# Power_Supply.net
KiCad netlist of a schematic drawn in Altium Designer
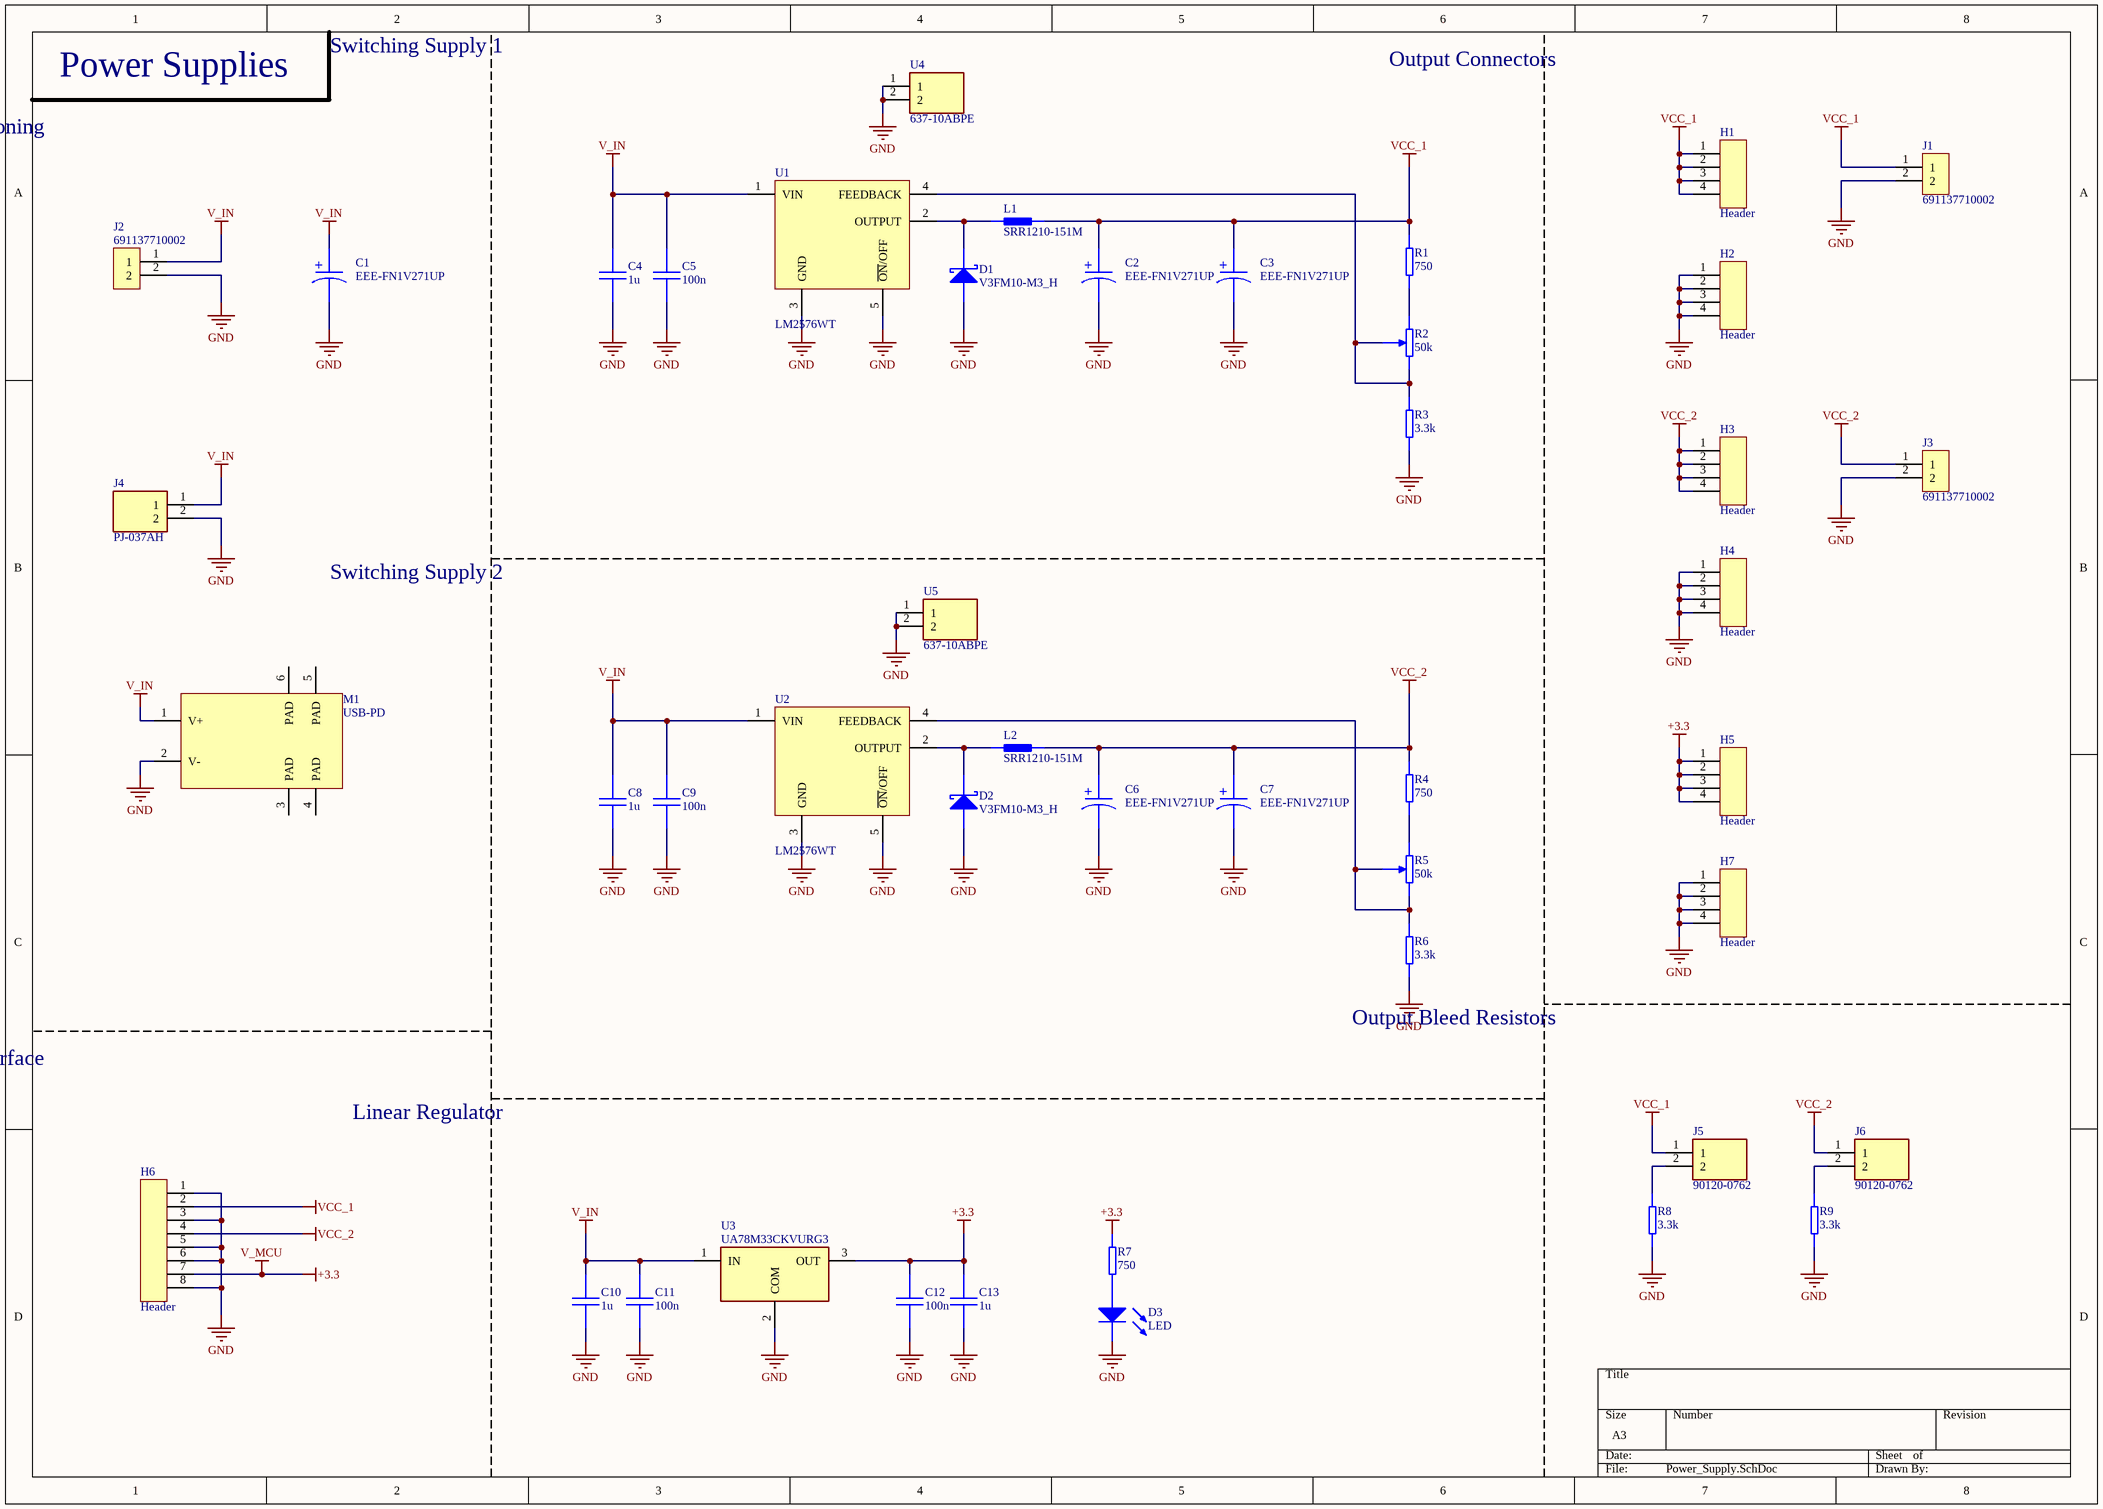
[diagram p0: Power_Supply.SchDoc]

(export (version "E")
  (design (tool "Eeschema 10.0.6"))
  (components
    (comp (ref "C1")
      (value "EEE-FN1V271UP")
      (footprint "EEHZT1E331UP")
      (description "Capacitor Polarised")
      (fields (field (name "MOUSER PART NUMBER") "667-EEE-FN1V271UP"))
      (libsource (lib "TD") (part "EEE-FN1V271UP"))
    )
    (comp (ref "C2")
      (value "EEE-FN1V271UP")
      (footprint "EEHZT1E331UP")
      (description "Capacitor Polarised")
      (fields (field (name "MOUSER PART NUMBER") "667-EEE-FN1V271UP"))
      (libsource (lib "TD") (part "EEE-FN1V271UP"))
    )
    (comp (ref "C3")
      (value "EEE-FN1V271UP")
      (footprint "EEHZT1E331UP")
      (description "Capacitor Polarised")
      (fields (field (name "MOUSER PART NUMBER") "667-EEE-FN1V271UP"))
      (libsource (lib "TD") (part "EEE-FN1V271UP"))
    )
    (comp (ref "C4")
      (value "1u")
      (footprint "CAP0805")
      (description "Non Polarized Capacitor")
      (libsource (lib "TD") (part "Capacitor - Non Polarized"))
    )
    (comp (ref "C5")
      (value "100n")
      (footprint "CAP0805")
      (description "Non Polarized Capacitor")
      (libsource (lib "TD") (part "Capacitor - Non Polarized"))
    )
    (comp (ref "C6")
      (value "EEE-FN1V271UP")
      (footprint "EEHZT1E331UP")
      (description "Capacitor Polarised")
      (fields (field (name "MOUSER PART NUMBER") "667-EEE-FN1V271UP"))
      (libsource (lib "TD") (part "EEE-FN1V271UP"))
    )
    (comp (ref "C7")
      (value "EEE-FN1V271UP")
      (footprint "EEHZT1E331UP")
      (description "Capacitor Polarised")
      (fields (field (name "MOUSER PART NUMBER") "667-EEE-FN1V271UP"))
      (libsource (lib "TD") (part "EEE-FN1V271UP"))
    )
    (comp (ref "C8")
      (value "1u")
      (footprint "CAP0805")
      (description "Non Polarized Capacitor")
      (libsource (lib "TD") (part "Capacitor - Non Polarized"))
    )
    (comp (ref "C9")
      (value "100n")
      (footprint "CAP0805")
      (description "Non Polarized Capacitor")
      (libsource (lib "TD") (part "Capacitor - Non Polarized"))
    )
    (comp (ref "C10")
      (value "1u")
      (footprint "CAP0805")
      (description "Non Polarized Capacitor")
      (libsource (lib "TD") (part "Capacitor - Non Polarized"))
    )
    (comp (ref "C11")
      (value "100n")
      (footprint "CAP0805")
      (description "Non Polarized Capacitor")
      (libsource (lib "TD") (part "Capacitor - Non Polarized"))
    )
    (comp (ref "C12")
      (value "100n")
      (footprint "CAP0805")
      (description "Non Polarized Capacitor")
      (libsource (lib "TD") (part "Capacitor - Non Polarized"))
    )
    (comp (ref "C13")
      (value "1u")
      (footprint "CAP0805")
      (description "Non Polarized Capacitor")
      (libsource (lib "TD") (part "Capacitor - Non Polarized"))
    )
    (comp (ref "D1")
      (value "V3FM10-M3_H")
      (footprint "DO-219AB")
      (description "Schottky Diode")
      (fields
        (field (name "MANUFACTURER_PART_NUMBER") "V3FM10-M3/H")
        (field (name "MOUSER PART NUMBER") "78-V3FM10-M3/H")
      )
      (libsource (lib "TD") (part "V3FM10-M3_H"))
    )
    (comp (ref "D2")
      (value "V3FM10-M3_H")
      (footprint "DO-219AB")
      (description "Schottky Diode")
      (fields
        (field (name "MANUFACTURER_PART_NUMBER") "V3FM10-M3/H")
        (field (name "MOUSER PART NUMBER") "78-V3FM10-M3/H")
      )
      (libsource (lib "TD") (part "V3FM10-M3_H"))
    )
    (comp (ref "D3")
      (value "LED")
      (footprint "LEDM2012X80N")
      (description "General Purpose LED")
      (libsource (lib "TD") (part "LED"))
    )
    (comp (ref "H1")
      (value "Header")
      (footprint "Header_1X4")
      (description "4-Pin Header")
      (libsource (lib "TD") (part "4-Pin Header"))
    )
    (comp (ref "H2")
      (value "Header")
      (footprint "Header_1X4")
      (description "4-Pin Header")
      (libsource (lib "TD") (part "4-Pin Header"))
    )
    (comp (ref "H3")
      (value "Header")
      (footprint "Header_1X4")
      (description "4-Pin Header")
      (libsource (lib "TD") (part "4-Pin Header"))
    )
    (comp (ref "H4")
      (value "Header")
      (footprint "Header_1X4")
      (description "4-Pin Header")
      (libsource (lib "TD") (part "4-Pin Header"))
    )
    (comp (ref "H5")
      (value "Header")
      (footprint "Header_1X4")
      (description "4-Pin Header")
      (libsource (lib "TD") (part "4-Pin Header"))
    )
    (comp (ref "H6")
      (value "Header")
      (footprint "Header_1X8")
      (description "8-Pin Header")
      (libsource (lib "TD") (part "8-Pin Header"))
    )
    (comp (ref "H7")
      (value "Header")
      (footprint "Header_1X4")
      (description "4-Pin Header")
      (libsource (lib "TD") (part "4-Pin Header"))
    )
    (comp (ref "J1")
      (value "691137710002")
      (footprint "SHDR2W70P0X500_1X2_1000X750X1160P")
      (description "Connector")
      (fields (field (name "MOUSER PART NUMBER") "710-691137710002"))
      (libsource (lib "") (part "691137710002_1"))
    )
    (comp (ref "J2")
      (value "691137710002")
      (footprint "SHDR2W70P0X500_1X2_1000X750X1160P")
      (description "Connector")
      (fields (field (name "MOUSER PART NUMBER") "710-691137710002"))
      (libsource (lib "TD") (part "691137710002"))
    )
    (comp (ref "J3")
      (value "691137710002")
      (footprint "SHDR2W70P0X500_1X2_1000X750X1160P")
      (description "Connector")
      (fields (field (name "MOUSER PART NUMBER") "710-691137710002"))
      (libsource (lib "") (part "691137710002_1"))
    )
    (comp (ref "J4")
      (value "PJ-037AH")
      (footprint "PJ037AH")
      (description "Connector")
      (fields (field (name "MOUSER PART NUMBER") "490-PJ-037AH"))
      (libsource (lib "TD") (part "PJ-037AH"))
    )
    (comp (ref "J5")
      (value "90120-0762")
      (footprint "HDRV2W35P0X254_1X2_508X249X560P")
      (description "Connector")
      (fields (field (name "MOUSER PART NUMBER") "538-90120-0762"))
      (libsource (lib "SamacSys") (part "90120-0762"))
    )
    (comp (ref "J6")
      (value "90120-0762")
      (footprint "HDRV2W35P0X254_1X2_508X249X560P")
      (description "Connector")
      (fields (field (name "MOUSER PART NUMBER") "538-90120-0762"))
      (libsource (lib "SamacSys") (part "90120-0762"))
    )
    (comp (ref "L1")
      (value "SRR1210-151M")
      (footprint "INDPM120120X1000N-D")
      (description "Inductor")
      (fields (field (name "MOUSER PART NUMBER") "652-SRR1210-151M"))
      (libsource (lib "TD") (part "SRR1210-151M"))
    )
    (comp (ref "L2")
      (value "SRR1210-151M")
      (footprint "INDPM120120X1000N-D")
      (description "Inductor")
      (fields (field (name "MOUSER PART NUMBER") "652-SRR1210-151M"))
      (libsource (lib "TD") (part "SRR1210-151M"))
    )
    (comp (ref "M1")
      (value "USB-PD")
      (footprint "USB_C-PD")
      (libsource (lib "IEEE_Workshop_SCH") (part "USB-PD"))
    )
    (comp (ref "R1")
      (value "750")
      (footprint "RESC0805")
      (description "Resistor")
      (libsource (lib "TD") (part "Resistor"))
    )
    (comp (ref "R2")
      (value "50k")
      (footprint "3339P1103LF")
      (description "Potentionmeter")
      (libsource (lib "TD") (part "Potentiometer"))
    )
    (comp (ref "R3")
      (value "3.3k")
      (footprint "RESC0805")
      (description "Resistor")
      (libsource (lib "TD") (part "Resistor"))
    )
    (comp (ref "R4")
      (value "750")
      (footprint "RESC0805")
      (description "Resistor")
      (libsource (lib "TD") (part "Resistor"))
    )
    (comp (ref "R5")
      (value "50k")
      (footprint "3339P1103LF")
      (description "Potentionmeter")
      (libsource (lib "TD") (part "Potentiometer"))
    )
    (comp (ref "R6")
      (value "3.3k")
      (footprint "RESC0805")
      (description "Resistor")
      (libsource (lib "TD") (part "Resistor"))
    )
    (comp (ref "R7")
      (value "750")
      (footprint "RESC0805")
      (description "Resistor")
      (libsource (lib "TD") (part "Resistor"))
    )
    (comp (ref "R8")
      (value "3.3k")
      (footprint "RESC0805")
      (description "Resistor")
      (libsource (lib "TD") (part "Resistor"))
    )
    (comp (ref "R9")
      (value "3.3k")
      (footprint "RESC0805")
      (description "Resistor")
      (libsource (lib "TD") (part "Resistor"))
    )
    (comp (ref "U1")
      (value "LM2576WT")
      (footprint "TO-220-5")
      (description "Integrated Circuit")
      (fields
        (field (name "MANUFACTURER_PART_NUMBER") "LM2576WU-TR")
        (field (name "MOUSER PART NUMBER") "998-LM2576WT")
      )
      (libsource (lib "IEEE_Workshop_Schematic_Symbols") (part "LM2576WT"))
    )
    (comp (ref "U2")
      (value "LM2576WT")
      (footprint "TO-220-5")
      (description "Integrated Circuit")
      (fields
        (field (name "MANUFACTURER_PART_NUMBER") "LM2576WU-TR")
        (field (name "MOUSER PART NUMBER") "998-LM2576WT")
      )
      (libsource (lib "IEEE_Workshop_Schematic_Symbols") (part "LM2576WT"))
    )
    (comp (ref "U3")
      (value "UA78M33CKVURG3")
      (footprint "TO-252-3")
      (description "Linear Voltage Regulator")
      (fields (field (name "MOUSER PART NUMBER") "595-UA78M33CKVURG3"))
      (libsource (lib "TD") (part "UA78M33CKVURG3"))
    )
    (comp (ref "U4")
      (value "637-10ABPE")
      (footprint "63710ABPE")
      (description "Undefined or Miscellaneous")
      (fields (field (name "MOUSER PART NUMBER") "567-637-10ABPE"))
      (libsource (lib "*") (part "637-10ABPE"))
    )
    (comp (ref "U5")
      (value "637-10ABPE")
      (footprint "63710ABPE")
      (description "Undefined or Miscellaneous")
      (fields (field (name "MOUSER PART NUMBER") "567-637-10ABPE"))
      (libsource (lib "*") (part "637-10ABPE"))
    )
  )
  (nets
    (net (code "1") (name "+3.3") (class "Default")
      (node (ref "C12") (pin "1") (pintype "passive"))
      (node (ref "C13") (pin "1") (pintype "passive"))
      (node (ref "H5") (pin "1") (pintype "passive"))
      (node (ref "H5") (pin "2") (pintype "passive"))
      (node (ref "H5") (pin "3") (pintype "passive"))
      (node (ref "H5") (pin "4") (pintype "passive"))
      (node (ref "H6") (pin "7") (pintype "passive"))
      (node (ref "R7") (pin "1") (pintype "passive"))
      (node (ref "U3") (pin "3") (pinfunction "OUT_3") (pintype "passive"))
    )
    (net (code "2") (name "GND") (class "Default")
      (node (ref "C1") (pin "2") (pintype "passive"))
      (node (ref "C10") (pin "2") (pintype "passive"))
      (node (ref "C11") (pin "2") (pintype "passive"))
      (node (ref "C12") (pin "2") (pintype "passive"))
      (node (ref "C13") (pin "2") (pintype "passive"))
      (node (ref "C2") (pin "2") (pintype "passive"))
      (node (ref "C3") (pin "2") (pintype "passive"))
      (node (ref "C4") (pin "2") (pintype "passive"))
      (node (ref "C5") (pin "2") (pintype "passive"))
      (node (ref "C6") (pin "2") (pintype "passive"))
      (node (ref "C7") (pin "2") (pintype "passive"))
      (node (ref "C8") (pin "2") (pintype "passive"))
      (node (ref "C9") (pin "2") (pintype "passive"))
      (node (ref "D1") (pin "2") (pinfunction "A_2") (pintype "passive"))
      (node (ref "D2") (pin "2") (pinfunction "A_2") (pintype "passive"))
      (node (ref "D3") (pin "1") (pinfunction "K_1") (pintype "passive"))
      (node (ref "H2") (pin "1") (pintype "passive"))
      (node (ref "H2") (pin "2") (pintype "passive"))
      (node (ref "H2") (pin "3") (pintype "passive"))
      (node (ref "H2") (pin "4") (pintype "passive"))
      (node (ref "H4") (pin "1") (pintype "passive"))
      (node (ref "H4") (pin "2") (pintype "passive"))
      (node (ref "H4") (pin "3") (pintype "passive"))
      (node (ref "H4") (pin "4") (pintype "passive"))
      (node (ref "H6") (pin "1") (pintype "passive"))
      (node (ref "H6") (pin "3") (pintype "passive"))
      (node (ref "H6") (pin "5") (pintype "passive"))
      (node (ref "H6") (pin "6") (pintype "passive"))
      (node (ref "H6") (pin "8") (pintype "passive"))
      (node (ref "H7") (pin "1") (pintype "passive"))
      (node (ref "H7") (pin "2") (pintype "passive"))
      (node (ref "H7") (pin "3") (pintype "passive"))
      (node (ref "H7") (pin "4") (pintype "passive"))
      (node (ref "J1") (pin "2") (pinfunction "2_2") (pintype "passive"))
      (node (ref "J2") (pin "2") (pinfunction "2_2") (pintype "passive"))
      (node (ref "J3") (pin "2") (pinfunction "2_2") (pintype "passive"))
      (node (ref "J4") (pin "2") (pinfunction "2_2") (pintype "passive"))
      (node (ref "M1") (pin "2") (pinfunction "V-_2") (pintype "passive"))
      (node (ref "R3") (pin "2") (pintype "passive"))
      (node (ref "R6") (pin "2") (pintype "passive"))
      (node (ref "R8") (pin "2") (pintype "passive"))
      (node (ref "R9") (pin "2") (pintype "passive"))
      (node (ref "U1") (pin "3") (pinfunction "GND_3") (pintype "passive"))
      (node (ref "U1") (pin "5") (pinfunction "~{ON}/OFF_5") (pintype "passive"))
      (node (ref "U2") (pin "3") (pinfunction "GND_3") (pintype "passive"))
      (node (ref "U2") (pin "5") (pinfunction "~{ON}/OFF_5") (pintype "passive"))
      (node (ref "U3") (pin "2") (pinfunction "COM_2") (pintype "passive"))
      (node (ref "U4") (pin "1") (pinfunction "1_1") (pintype "passive"))
      (node (ref "U4") (pin "2") (pinfunction "2_2") (pintype "passive"))
      (node (ref "U5") (pin "1") (pinfunction "1_1") (pintype "passive"))
      (node (ref "U5") (pin "2") (pinfunction "2_2") (pintype "passive"))
    )
    (net (code "3") (name "Net-(D1-K)") (class "Default")
      (node (ref "D1") (pin "1") (pinfunction "K_1") (pintype "passive"))
      (node (ref "L1") (pin "1") (pintype "passive"))
      (node (ref "U1") (pin "2") (pinfunction "OUTPUT_2") (pintype "passive"))
    )
    (net (code "4") (name "Net-(D2-K)") (class "Default")
      (node (ref "D2") (pin "1") (pinfunction "K_1") (pintype "passive"))
      (node (ref "L2") (pin "1") (pintype "passive"))
      (node (ref "U2") (pin "2") (pinfunction "OUTPUT_2") (pintype "passive"))
    )
    (net (code "5") (name "Net-(D3-A)") (class "Default")
      (node (ref "D3") (pin "2") (pinfunction "A_2") (pintype "passive"))
      (node (ref "R7") (pin "2") (pintype "passive"))
    )
    (net (code "6") (name "Net-(J5-Pad2)") (class "Default")
      (node (ref "J5") (pin "2") (pinfunction "2_2") (pintype "passive"))
      (node (ref "R8") (pin "1") (pintype "passive"))
    )
    (net (code "7") (name "Net-(J6-Pad2)") (class "Default")
      (node (ref "J6") (pin "2") (pinfunction "2_2") (pintype "passive"))
      (node (ref "R9") (pin "1") (pintype "passive"))
    )
    (net (code "8") (name "Net-(R1-Pad2)") (class "Default")
      (node (ref "R1") (pin "2") (pintype "passive"))
      (node (ref "R2") (pin "1") (pintype "passive"))
    )
    (net (code "9") (name "Net-(R4-Pad2)") (class "Default")
      (node (ref "R4") (pin "2") (pintype "passive"))
      (node (ref "R5") (pin "1") (pintype "passive"))
    )
    (net (code "10") (name "Net-(U1-FEEDBACK)") (class "Default")
      (node (ref "R2") (pin "2") (pintype "passive"))
      (node (ref "R2") (pin "3") (pintype "passive"))
      (node (ref "R3") (pin "1") (pintype "passive"))
      (node (ref "U1") (pin "4") (pinfunction "FEEDBACK_4") (pintype "passive"))
    )
    (net (code "11") (name "Net-(U2-FEEDBACK)") (class "Default")
      (node (ref "R5") (pin "2") (pintype "passive"))
      (node (ref "R5") (pin "3") (pintype "passive"))
      (node (ref "R6") (pin "1") (pintype "passive"))
      (node (ref "U2") (pin "4") (pinfunction "FEEDBACK_4") (pintype "passive"))
    )
    (net (code "12") (name "VCC_1") (class "Default")
      (node (ref "C2") (pin "1") (pintype "passive"))
      (node (ref "C3") (pin "1") (pintype "passive"))
      (node (ref "H1") (pin "1") (pintype "passive"))
      (node (ref "H1") (pin "2") (pintype "passive"))
      (node (ref "H1") (pin "3") (pintype "passive"))
      (node (ref "H1") (pin "4") (pintype "passive"))
      (node (ref "H6") (pin "2") (pintype "passive"))
      (node (ref "J1") (pin "1") (pinfunction "1_1") (pintype "passive"))
      (node (ref "J5") (pin "1") (pinfunction "1_1") (pintype "passive"))
      (node (ref "L1") (pin "2") (pintype "passive"))
      (node (ref "R1") (pin "1") (pintype "passive"))
    )
    (net (code "13") (name "VCC_2") (class "Default")
      (node (ref "C6") (pin "1") (pintype "passive"))
      (node (ref "C7") (pin "1") (pintype "passive"))
      (node (ref "H3") (pin "1") (pintype "passive"))
      (node (ref "H3") (pin "2") (pintype "passive"))
      (node (ref "H3") (pin "3") (pintype "passive"))
      (node (ref "H3") (pin "4") (pintype "passive"))
      (node (ref "H6") (pin "4") (pintype "passive"))
      (node (ref "J3") (pin "1") (pinfunction "1_1") (pintype "passive"))
      (node (ref "J6") (pin "1") (pinfunction "1_1") (pintype "passive"))
      (node (ref "L2") (pin "2") (pintype "passive"))
      (node (ref "R4") (pin "1") (pintype "passive"))
    )
    (net (code "14") (name "V_IN") (class "Default")
      (node (ref "C1") (pin "1") (pintype "passive"))
      (node (ref "C10") (pin "1") (pintype "passive"))
      (node (ref "C11") (pin "1") (pintype "passive"))
      (node (ref "C4") (pin "1") (pintype "passive"))
      (node (ref "C5") (pin "1") (pintype "passive"))
      (node (ref "C8") (pin "1") (pintype "passive"))
      (node (ref "C9") (pin "1") (pintype "passive"))
      (node (ref "J2") (pin "1") (pinfunction "1_1") (pintype "passive"))
      (node (ref "J4") (pin "1") (pinfunction "1_1") (pintype "passive"))
      (node (ref "M1") (pin "1") (pinfunction "V+_1") (pintype "passive"))
      (node (ref "U1") (pin "1") (pinfunction "VIN_1") (pintype "passive"))
      (node (ref "U2") (pin "1") (pinfunction "VIN_1") (pintype "passive"))
      (node (ref "U3") (pin "1") (pinfunction "IN_1") (pintype "passive"))
    )
    (net (code "15") (name "unconnected-(M1-PAD-Pad3)") (class "Default")
      (node (ref "M1") (pin "3") (pinfunction "PAD_3") (pintype "passive"))
    )
    (net (code "16") (name "unconnected-(M1-PAD-Pad4)") (class "Default")
      (node (ref "M1") (pin "4") (pinfunction "PAD_4") (pintype "passive"))
    )
    (net (code "17") (name "unconnected-(M1-PAD-Pad5)") (class "Default")
      (node (ref "M1") (pin "5") (pinfunction "PAD_5") (pintype "passive"))
    )
    (net (code "18") (name "unconnected-(M1-PAD-Pad6)") (class "Default")
      (node (ref "M1") (pin "6") (pinfunction "PAD_6") (pintype "passive"))
    )
  )
)
